# P_iron_V3_0_2020-11-07_23-12-25.net
KiCad netlist of a schematic drawn in Altium Designer
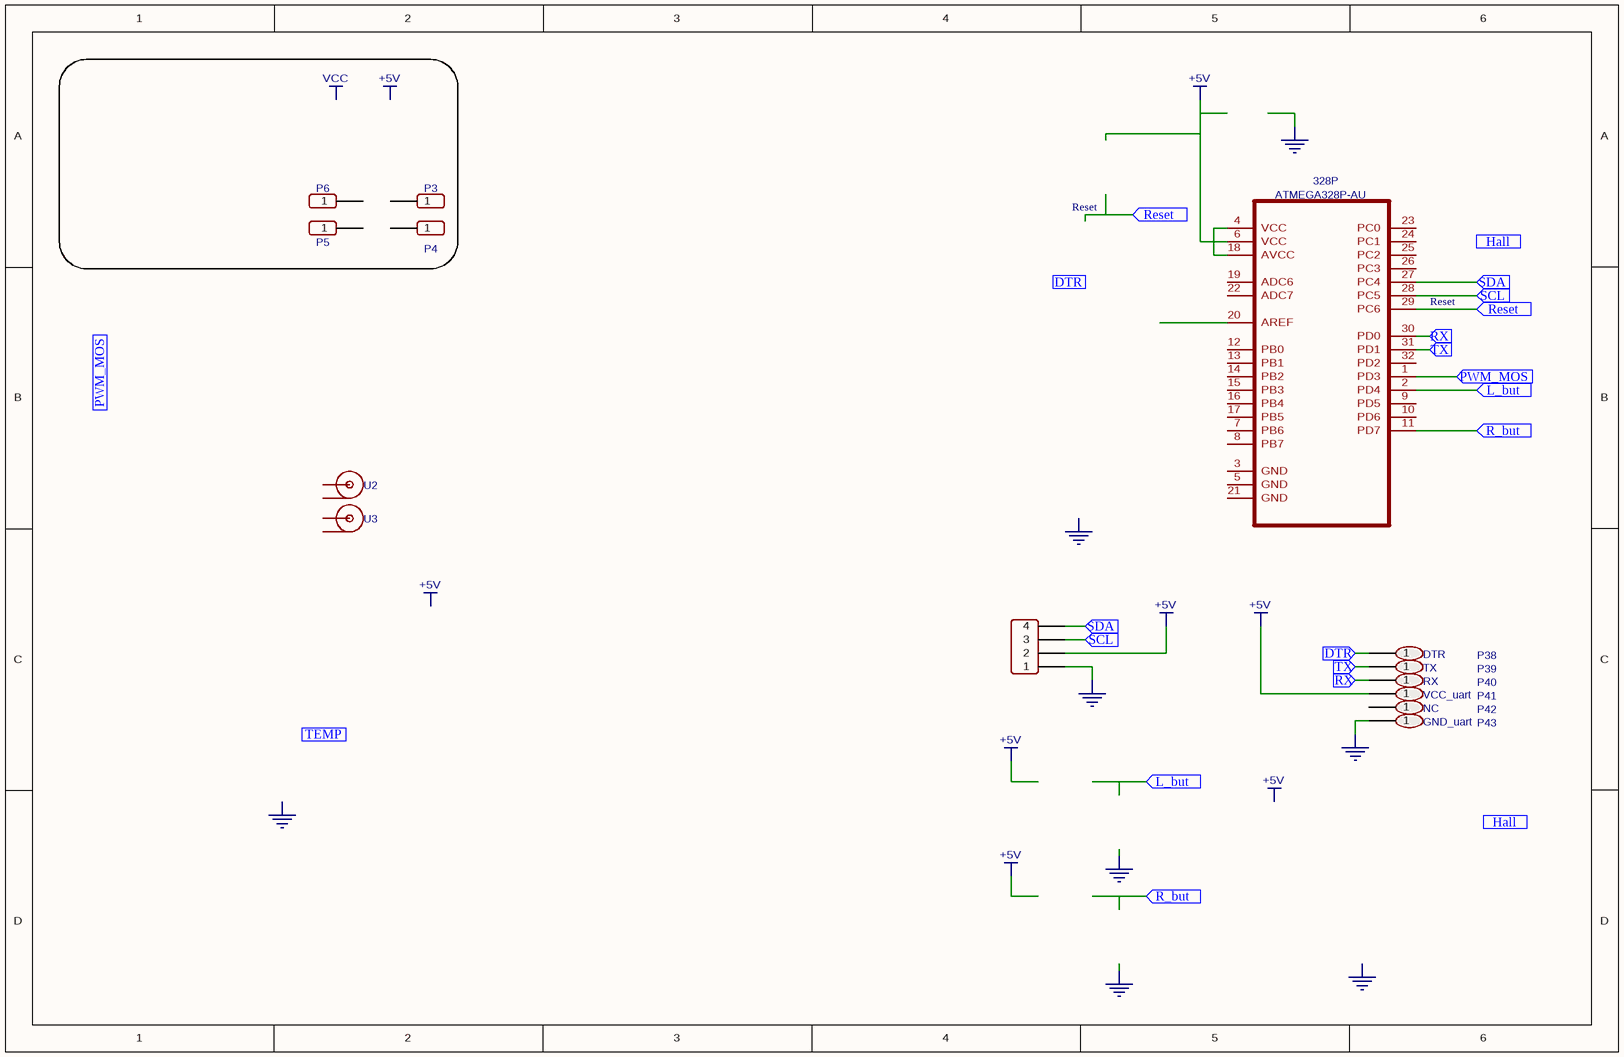
[diagram p0: P_iron_V3.0_2020-11-07_23-12-25.schdoc]

(export (version "E")
  (design (tool "Eeschema 10.0.6"))
  (components
    (comp (ref "328P")
      (value "ATMEGA328P-AU")
      (fields (field (name "BOM_MANUFACTURER PART") "?"))
      (libsource (lib "altium-import") (part "root_0_ATMEGA328P-AU_"))
    )
    (comp (ref "P1")
      (value "i2c_OLED")
      (fields
        (field (name "BOM_MANUFACTURER PART") "Headers  Pins 1*4P")
        (field (name "BOM_SUPPLIER PART") "undefined")
      )
      (libsource (lib "altium-import") (part "root_2_i2c_OLED_"))
    )
    (comp (ref "P3")
      (value "Header 1*1P")
      (fields (field (name "BOM_SUPPLIER PART") "C81276"))
      (libsource (lib "altium-import") (part "root_0_Header 1*1P_"))
    )
    (comp (ref "P4")
      (value "Header 1*1P")
      (fields (field (name "BOM_SUPPLIER PART") "C81276"))
      (libsource (lib "altium-import") (part "root_0_Header 1*1P_"))
    )
    (comp (ref "P5")
      (value "Header 1*1P")
      (fields (field (name "BOM_SUPPLIER PART") "C81276"))
      (libsource (lib "altium-import") (part "root_2_Header 1*1P_"))
    )
    (comp (ref "P6")
      (value "Header 1*1P")
      (fields (field (name "BOM_SUPPLIER PART") "C81276"))
      (libsource (lib "altium-import") (part "root_2_Header 1*1P_"))
    )
    (comp (ref "P38")
      (value "DTR")
      (fields
        (field (name "BOM_MANUFACTURER PART") "Header 1*1P")
        (field (name "BOM_SUPPLIER PART") "C81276")
      )
      (libsource (lib "altium-import") (part "root_0_DTR_"))
    )
    (comp (ref "P39")
      (value "TX")
      (fields
        (field (name "BOM_MANUFACTURER PART") "Header 1*1P")
        (field (name "BOM_SUPPLIER PART") "C81276")
      )
      (libsource (lib "altium-import") (part "root_0_TX_"))
    )
    (comp (ref "P40")
      (value "RX")
      (fields
        (field (name "BOM_MANUFACTURER PART") "Header 1*1P")
        (field (name "BOM_SUPPLIER PART") "C81276")
      )
      (libsource (lib "altium-import") (part "root_0_RX_"))
    )
    (comp (ref "P41")
      (value "VCC_uart")
      (fields
        (field (name "BOM_MANUFACTURER PART") "Header 1*1P")
        (field (name "BOM_SUPPLIER PART") "C81276")
      )
      (libsource (lib "altium-import") (part "root_0_VCC_uart_"))
    )
    (comp (ref "P42")
      (value "NC")
      (fields
        (field (name "BOM_MANUFACTURER PART") "Header 1*1P")
        (field (name "BOM_SUPPLIER PART") "C81276")
      )
      (libsource (lib "altium-import") (part "root_0_NC_"))
    )
    (comp (ref "P43")
      (value "GND_uart")
      (fields
        (field (name "BOM_MANUFACTURER PART") "Header 1*1P")
        (field (name "BOM_SUPPLIER PART") "C81276")
      )
      (libsource (lib "altium-import") (part "root_0_GND_uart_"))
    )
    (comp (ref "U2")
      (value "Fuse clip 1p TH")
      (fields
        (field (name "BOM_MANUFACTURER PART") "5x20 RHOS Fuse clip/seat")
        (field (name "BOM_SUPPLIER PART") "C3130")
        (field (name "CONTRIBUTOR") "gjt211")
      )
      (libsource (lib "altium-import") (part "root_0_Fuse clip 1p TH_"))
    )
    (comp (ref "U3")
      (value "Fuse clip 1p TH")
      (fields
        (field (name "BOM_MANUFACTURER PART") "5x20 RHOS Fuse clip/seat")
        (field (name "BOM_SUPPLIER PART") "C3130")
        (field (name "CONTRIBUTOR") "gjt211")
      )
      (libsource (lib "altium-import") (part "root_0_Fuse clip 1p TH_"))
    )
  )
  (nets
    (net (code "1") (name "+5V") (class "Default")
      (node (ref "328P") (pin "18") (pinfunction "AVCC_18") (pintype "passive"))
      (node (ref "328P") (pin "4") (pinfunction "VCC_4") (pintype "passive"))
      (node (ref "328P") (pin "6") (pinfunction "VCC_6") (pintype "passive"))
      (node (ref "P1") (pin "2") (pinfunction "2_2") (pintype "passive"))
      (node (ref "P41") (pin "1") (pinfunction "1_1") (pintype "passive"))
    )
    (net (code "2") (name "/DTR") (class "Default")
      (node (ref "P38") (pin "1") (pinfunction "1_1") (pintype "passive"))
    )
    (net (code "4") (name "/L_but") (class "Default")
      (node (ref "328P") (pin "2") (pinfunction "PD4_2") (pintype "passive"))
    )
    (net (code "5") (name "/PWM_MOS") (class "Default")
      (node (ref "328P") (pin "1") (pinfunction "PD3_1") (pintype "passive"))
    )
    (net (code "6") (name "/RX") (class "Default")
      (node (ref "328P") (pin "30") (pinfunction "PD0_30") (pintype "passive"))
      (node (ref "P40") (pin "1") (pinfunction "1_1") (pintype "passive"))
    )
    (net (code "7") (name "/R_but") (class "Default")
      (node (ref "328P") (pin "11") (pinfunction "PD7_11") (pintype "passive"))
    )
    (net (code "8") (name "/Reset") (class "Default")
      (node (ref "328P") (pin "29") (pinfunction "PC6_29") (pintype "passive"))
    )
    (net (code "9") (name "/SCL") (class "Default")
      (node (ref "328P") (pin "28") (pinfunction "PC5_28") (pintype "passive"))
      (node (ref "P1") (pin "3") (pinfunction "3_3") (pintype "passive"))
    )
    (net (code "10") (name "/SDA") (class "Default")
      (node (ref "328P") (pin "27") (pinfunction "PC4_27") (pintype "passive"))
      (node (ref "P1") (pin "4") (pinfunction "4_4") (pintype "passive"))
    )
    (net (code "12") (name "/TX") (class "Default")
      (node (ref "328P") (pin "31") (pinfunction "PD1_31") (pintype "passive"))
      (node (ref "P39") (pin "1") (pinfunction "1_1") (pintype "passive"))
    )
    (net (code "13") (name "GND") (class "Default")
      (node (ref "P1") (pin "1") (pinfunction "1_1") (pintype "passive"))
      (node (ref "P43") (pin "1") (pinfunction "1_1") (pintype "passive"))
    )
    (net (code "15") (name "unconnected-(328P-ADC6-Pad19)") (class "Default")
      (node (ref "328P") (pin "19") (pinfunction "ADC6_19") (pintype "passive"))
    )
    (net (code "16") (name "unconnected-(328P-ADC7-Pad22)") (class "Default")
      (node (ref "328P") (pin "22") (pinfunction "ADC7_22") (pintype "passive"))
    )
    (net (code "17") (name "unconnected-(328P-AREF-Pad20)") (class "Default")
      (node (ref "328P") (pin "20") (pinfunction "AREF_20") (pintype "passive"))
    )
    (net (code "18") (name "unconnected-(328P-GND-Pad3)") (class "Default")
      (node (ref "328P") (pin "3") (pinfunction "GND_3") (pintype "passive"))
    )
    (net (code "19") (name "unconnected-(328P-GND-Pad5)") (class "Default")
      (node (ref "328P") (pin "5") (pinfunction "GND_5") (pintype "passive"))
    )
    (net (code "20") (name "unconnected-(328P-GND-Pad21)") (class "Default")
      (node (ref "328P") (pin "21") (pinfunction "GND_21") (pintype "passive"))
    )
    (net (code "21") (name "unconnected-(328P-PB0-Pad12)") (class "Default")
      (node (ref "328P") (pin "12") (pinfunction "PB0_12") (pintype "passive"))
    )
    (net (code "22") (name "unconnected-(328P-PB1-Pad13)") (class "Default")
      (node (ref "328P") (pin "13") (pinfunction "PB1_13") (pintype "passive"))
    )
    (net (code "23") (name "unconnected-(328P-PB2-Pad14)") (class "Default")
      (node (ref "328P") (pin "14") (pinfunction "PB2_14") (pintype "passive"))
    )
    (net (code "24") (name "unconnected-(328P-PB3-Pad15)") (class "Default")
      (node (ref "328P") (pin "15") (pinfunction "PB3_15") (pintype "passive"))
    )
    (net (code "25") (name "unconnected-(328P-PB4-Pad16)") (class "Default")
      (node (ref "328P") (pin "16") (pinfunction "PB4_16") (pintype "passive"))
    )
    (net (code "26") (name "unconnected-(328P-PB5-Pad17)") (class "Default")
      (node (ref "328P") (pin "17") (pinfunction "PB5_17") (pintype "passive"))
    )
    (net (code "27") (name "unconnected-(328P-PB6-Pad7)") (class "Default")
      (node (ref "328P") (pin "7") (pinfunction "PB6_7") (pintype "passive"))
    )
    (net (code "28") (name "unconnected-(328P-PB7-Pad8)") (class "Default")
      (node (ref "328P") (pin "8") (pinfunction "PB7_8") (pintype "passive"))
    )
    (net (code "29") (name "unconnected-(328P-PC0-Pad23)") (class "Default")
      (node (ref "328P") (pin "23") (pinfunction "PC0_23") (pintype "passive"))
    )
    (net (code "30") (name "unconnected-(328P-PC1-Pad24)") (class "Default")
      (node (ref "328P") (pin "24") (pinfunction "PC1_24") (pintype "passive"))
    )
    (net (code "31") (name "unconnected-(328P-PC2-Pad25)") (class "Default")
      (node (ref "328P") (pin "25") (pinfunction "PC2_25") (pintype "passive"))
    )
    (net (code "32") (name "unconnected-(328P-PC3-Pad26)") (class "Default")
      (node (ref "328P") (pin "26") (pinfunction "PC3_26") (pintype "passive"))
    )
    (net (code "33") (name "unconnected-(328P-PD2-Pad32)") (class "Default")
      (node (ref "328P") (pin "32") (pinfunction "PD2_32") (pintype "passive"))
    )
    (net (code "34") (name "unconnected-(328P-PD5-Pad9)") (class "Default")
      (node (ref "328P") (pin "9") (pinfunction "PD5_9") (pintype "passive"))
    )
    (net (code "35") (name "unconnected-(328P-PD6-Pad10)") (class "Default")
      (node (ref "328P") (pin "10") (pinfunction "PD6_10") (pintype "passive"))
    )
    (net (code "36") (name "unconnected-(P3-Pad1)") (class "Default")
      (node (ref "P3") (pin "1") (pinfunction "1_1") (pintype "passive"))
    )
    (net (code "37") (name "unconnected-(P4-Pad1)") (class "Default")
      (node (ref "P4") (pin "1") (pinfunction "1_1") (pintype "passive"))
    )
    (net (code "38") (name "unconnected-(P5-Pad1)") (class "Default")
      (node (ref "P5") (pin "1") (pinfunction "1_1") (pintype "passive"))
    )
    (net (code "39") (name "unconnected-(P6-Pad1)") (class "Default")
      (node (ref "P6") (pin "1") (pinfunction "1_1") (pintype "passive"))
    )
    (net (code "40") (name "unconnected-(P42-Pad1)") (class "Default")
      (node (ref "P42") (pin "1") (pinfunction "1_1") (pintype "passive"))
    )
    (net (code "41") (name "unconnected-(U2-Pad1)") (class "Default")
      (node (ref "U2") (pin "1") (pinfunction "1_1") (pintype "passive"))
    )
    (net (code "42") (name "unconnected-(U2-Pad1)_1") (class "Default")
      (node (ref "U2") (pin "1") (pinfunction "1_1") (pintype "passive"))
    )
    (net (code "43") (name "unconnected-(U3-Pad1)") (class "Default")
      (node (ref "U3") (pin "1") (pinfunction "1_1") (pintype "passive"))
    )
    (net (code "44") (name "unconnected-(U3-Pad1)_1") (class "Default")
      (node (ref "U3") (pin "1") (pinfunction "1_1") (pintype "passive"))
    )
  )
)
